# Motor_1.net
KiCad netlist of a schematic drawn in Altium Designer
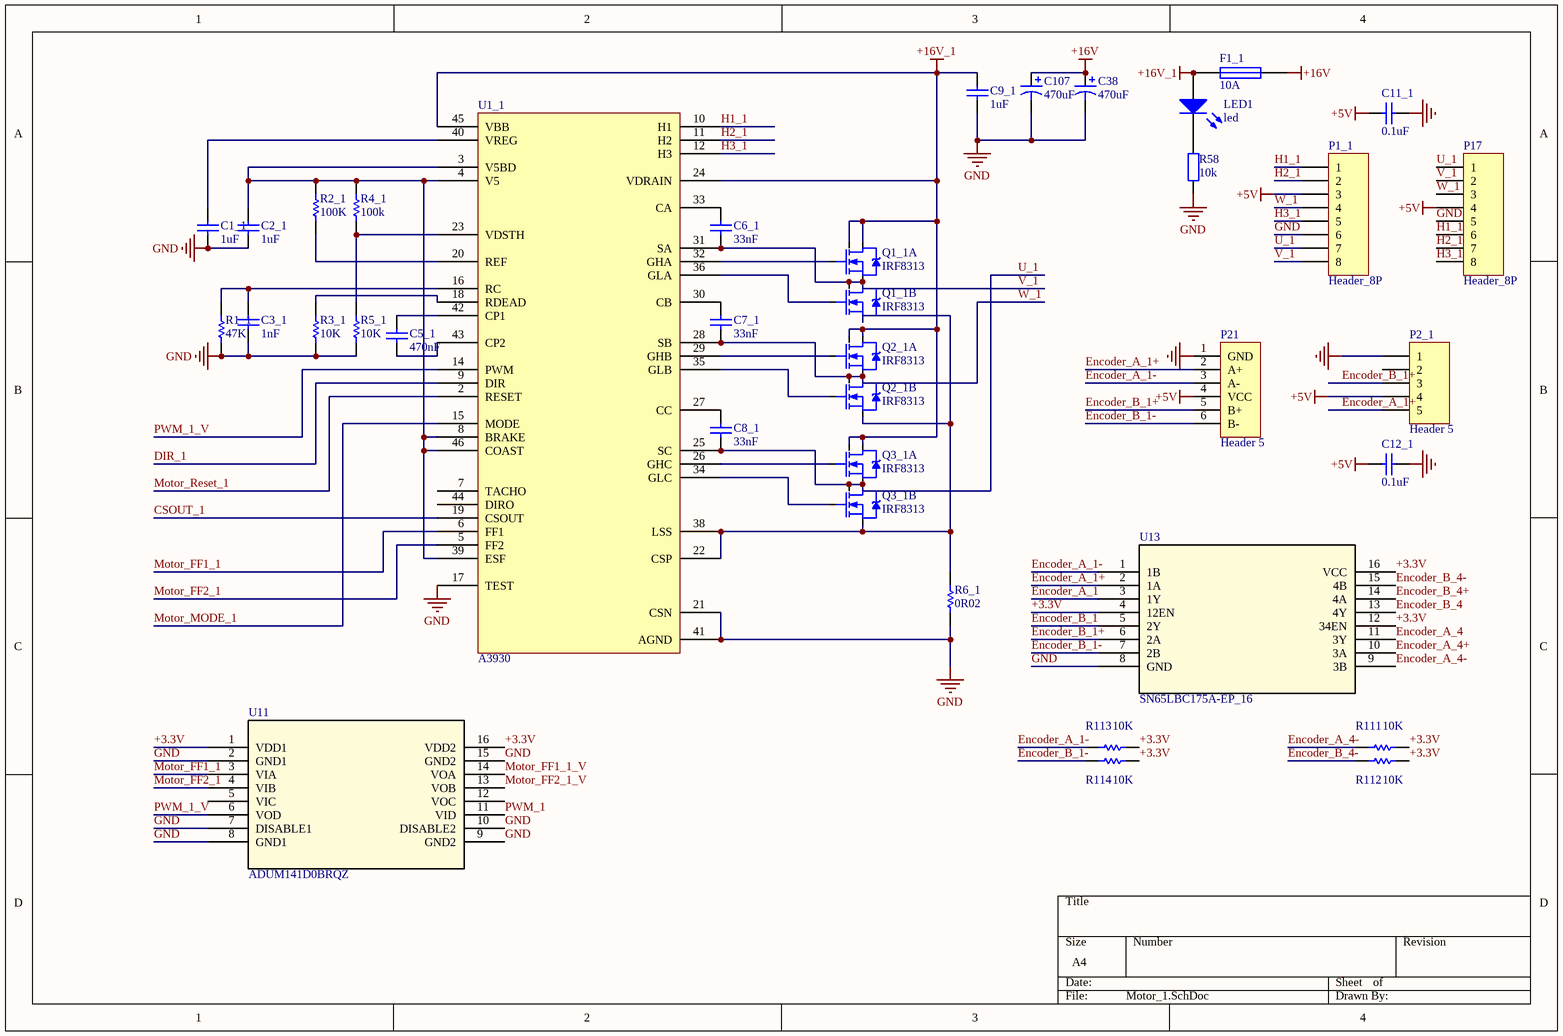
[diagram p0: Motor_1.SchDoc]

(export (version "E")
  (design (tool "Eeschema 10.0.6"))
  (components
    (comp (ref "C1_1")
      (value "1uF")
      (footprint "0603C")
      (description "Capacitor")
      (fields
        (field (name "MANUFACTURER") "Generic Components")
        (field (name "Comment") "1uf")
        (field (name "PUBLISHER") "Altium Hobart Technology Centre")
      )
      (libsource (lib "hp_2018_03") (part "Cap"))
    )
    (comp (ref "C2_1")
      (value "1uF")
      (footprint "0603C")
      (description "Capacitor")
      (fields
        (field (name "MANUFACTURER") "Generic Components")
        (field (name "Comment") "1uf")
        (field (name "PUBLISHER") "Altium Hobart Technology Centre")
      )
      (libsource (lib "hp_2018_03") (part "Cap"))
    )
    (comp (ref "C3_1")
      (value "1nF")
      (footprint "0603C")
      (description "Capacitor")
      (fields
        (field (name "MANUFACTURER") "Generic Components")
        (field (name "Comment") "1nf")
        (field (name "PUBLISHER") "Altium Hobart Technology Centre")
      )
      (libsource (lib "hp_2018_03") (part "Cap"))
    )
    (comp (ref "C5_1")
      (value "470nF")
      (footprint "0603C")
      (description "Capacitor")
      (fields
        (field (name "MANUFACTURER") "Generic Components")
        (field (name "Comment") "470nf")
        (field (name "PUBLISHER") "Altium Hobart Technology Centre")
      )
      (libsource (lib "hp_2018_03") (part "Cap"))
    )
    (comp (ref "C6_1")
      (value "33nF")
      (footprint "0603C")
      (description "Capacitor")
      (fields
        (field (name "MANUFACTURER") "Generic Components")
        (field (name "Comment") "33nf")
        (field (name "PUBLISHER") "Altium Hobart Technology Centre")
      )
      (libsource (lib "hp_2018_03") (part "Cap"))
    )
    (comp (ref "C7_1")
      (value "33nF")
      (footprint "0603C")
      (description "Capacitor")
      (fields
        (field (name "MANUFACTURER") "Generic Components")
        (field (name "Comment") "33nf")
        (field (name "PUBLISHER") "Altium Hobart Technology Centre")
      )
      (libsource (lib "hp_2018_03") (part "Cap"))
    )
    (comp (ref "C8_1")
      (value "33nF")
      (footprint "0603C")
      (description "Capacitor")
      (fields
        (field (name "MANUFACTURER") "Generic Components")
        (field (name "Comment") "33nf")
        (field (name "PUBLISHER") "Altium Hobart Technology Centre")
      )
      (libsource (lib "hp_2018_03") (part "Cap"))
    )
    (comp (ref "C9_1")
      (value "1uF")
      (footprint "0603C")
      (description "Capacitor")
      (fields
        (field (name "MANUFACTURER") "Generic Components")
        (field (name "Comment") "1uf")
        (field (name "PUBLISHER") "Altium Hobart Technology Centre")
      )
      (libsource (lib "hp_2018_03") (part "Cap"))
    )
    (comp (ref "C11_1")
      (value "0.1uF")
      (footprint "0603C")
      (description "Capacitor")
      (fields
        (field (name "MANUFACTURER") "Generic Components")
        (field (name "Comment") "0.1uf")
        (field (name "PUBLISHER") "Altium Hobart Technology Centre")
      )
      (libsource (lib "hp_2018_03") (part "Cap"))
    )
    (comp (ref "C12_1")
      (value "0.1uF")
      (footprint "0603C")
      (description "Capacitor")
      (fields
        (field (name "MANUFACTURER") "Generic Components")
        (field (name "Comment") "0.1uf")
        (field (name "PUBLISHER") "Altium Hobart Technology Centre")
      )
      (libsource (lib "hp_2018_03") (part "Cap"))
    )
    (comp (ref "C38")
      (value "470uF")
      (footprint "470uF")
      (description "Polarized Capacitor (Radial)")
      (fields (field (name "PUBLISHER") "Altium Limited"))
      (libsource (lib "Miscellaneous Devices") (part "Cap Pol1"))
    )
    (comp (ref "C107")
      (value "470uF")
      (footprint "470uF")
      (description "Polarized Capacitor (Radial)")
      (fields (field (name "PUBLISHER") "Altium Limited"))
      (libsource (lib "Miscellaneous Devices") (part "Cap Pol1"))
    )
    (comp (ref "F1_1")
      (value "10A")
      (footprint "Main_Board:FUSE_HEADER")
      (libsource (lib "Integrated_Library2") (part "FUSE"))
    )
    (comp (ref "LED1")
      (value "led")
      (footprint "0603_diode")
      (libsource (lib "Integrated_Library2") (part "led"))
    )
    (comp (ref "P1_1")
      (value "Header_8P")
      (footprint "8P - WF25122")
      (description "Used for Motor connection in ZJUNlict")
      (libsource (lib "Integrated_Library2") (part "Header_8P"))
    )
    (comp (ref "P2_1")
      (value "Header 5")
      (footprint "SHDR5")
      (description "Header, 5-Pin")
      (fields (field (name "PUBLISHER") "Altium Limited"))
      (libsource (lib "Miscellaneous Connectors") (part "Header 5"))
    )
    (comp (ref "P17")
      (value "Header_8P")
      (footprint "SHDR8")
      (description "Used for Motor connection in ZJUNlict")
      (libsource (lib "Integrated_Library2") (part "Header_8P"))
    )
    (comp (ref "P21")
      (value "Header 5")
      (footprint "SHDR6")
      (description "Header, 5-Pin")
      (fields (field (name "PUBLISHER") "Altium Limited"))
      (libsource (lib "Main_Board") (part "Header 6"))
    )
    (comp (ref "Q1_1") (value "IRF8313") (footprint "so-8 bg") (libsource (lib "BLDC") (part "SO-8 IRF8313")))
    (comp (ref "Q2_1") (value "IRF8313") (footprint "so-8 bg") (libsource (lib "BLDC") (part "SO-8 IRF8313")))
    (comp (ref "Q3_1") (value "IRF8313") (footprint "so-8 bg") (libsource (lib "BLDC") (part "SO-8 IRF8313")))
    (comp (ref "R1_1")
      (value "47K")
      (footprint "0603R")
      (description "Resistor")
      (fields
        (field (name "MANUFACTURER") "Generic Components")
        (field (name "Comment") "47k")
        (field (name "PUBLISHER") "Altium Hobart Technology Centre")
      )
      (libsource (lib "hp_2018_03") (part "Res1"))
    )
    (comp (ref "R2_1")
      (value "100K")
      (footprint "0603R")
      (description "Resistor")
      (fields
        (field (name "MANUFACTURER") "Generic Components")
        (field (name "Comment") "100k")
        (field (name "PUBLISHER") "Altium Hobart Technology Centre")
      )
      (libsource (lib "hp_2018_03") (part "Res1"))
    )
    (comp (ref "R3_1")
      (value "10K")
      (footprint "0603R")
      (description "Resistor")
      (fields
        (field (name "MANUFACTURER") "Generic Components")
        (field (name "Comment") "10k")
        (field (name "PUBLISHER") "Altium Hobart Technology Centre")
      )
      (libsource (lib "hp_2018_03") (part "Res1"))
    )
    (comp (ref "R4_1")
      (value "100k")
      (footprint "0603R")
      (description "Resistor")
      (fields
        (field (name "MANUFACTURER") "Generic Components")
        (field (name "PUBLISHER") "Altium Hobart Technology Centre")
      )
      (libsource (lib "hp_2018_03") (part "Res1"))
    )
    (comp (ref "R5_1")
      (value "10K")
      (footprint "0603R")
      (description "Resistor")
      (fields
        (field (name "MANUFACTURER") "Generic Components")
        (field (name "Comment") "10k")
        (field (name "PUBLISHER") "Altium Hobart Technology Centre")
      )
      (libsource (lib "hp_2018_03") (part "Res1"))
    )
    (comp (ref "R6_1")
      (value "0R02")
      (footprint "1206 10A")
      (description "Resistor")
      (fields
        (field (name "MANUFACTURER") "Generic Components")
        (field (name "Comment") "0.02")
        (field (name "PUBLISHER") "Altium Hobart Technology Centre")
      )
      (libsource (lib "hp_2018_03") (part "Res1"))
    )
    (comp (ref "R58") (value "10k") (footprint "0603") (libsource (lib "Integrated_Library2") (part "res")))
    (comp (ref "R111")
      (value "10K")
      (footprint "0603R")
      (description "Resistor")
      (fields
        (field (name "MANUFACTURER") "Generic Components")
        (field (name "Comment") "10k")
        (field (name "PUBLISHER") "Altium Hobart Technology Centre")
      )
      (libsource (lib "hp_2018_03") (part "Res1"))
    )
    (comp (ref "R112")
      (value "10K")
      (footprint "0603R")
      (description "Resistor")
      (fields
        (field (name "MANUFACTURER") "Generic Components")
        (field (name "Comment") "10k")
        (field (name "PUBLISHER") "Altium Hobart Technology Centre")
      )
      (libsource (lib "hp_2018_03") (part "Res1"))
    )
    (comp (ref "R113")
      (value "10K")
      (footprint "0603R")
      (description "Resistor")
      (fields
        (field (name "MANUFACTURER") "Generic Components")
        (field (name "Comment") "10k")
        (field (name "PUBLISHER") "Altium Hobart Technology Centre")
      )
      (libsource (lib "hp_2018_03") (part "Res1"))
    )
    (comp (ref "R114")
      (value "10K")
      (footprint "0603R")
      (description "Resistor")
      (fields
        (field (name "MANUFACTURER") "Generic Components")
        (field (name "Comment") "10k")
        (field (name "PUBLISHER") "Altium Hobart Technology Centre")
      )
      (libsource (lib "hp_2018_03") (part "Res1"))
    )
    (comp (ref "U1_1") (value "A3930") (footprint "LQFP-48") (libsource (lib "BLDC") (part "LQFP 48")))
    (comp (ref "U11")
      (value "ADUM141D0BRQZ")
      (footprint "Main_Board:RQ_16")
      (description "Imported")
      (libsource (lib "Main_Board") (part "ADUM141D0BRQZ"))
    )
    (comp (ref "U13")
      (value "SN65LBC175A-EP_16")
      (footprint "SOP16")
      (description "Quadruple 2-Input Positive-NAND Gates")
      (fields
        (field (name "MANUFACTURER") "Texas Instruments")
        (field (name "GENERIC_PART_NUMBER") "74AC11000")
      )
      (libsource (lib "Main_Board") (part "SN65LBC175A-EP_16"))
    )
  )
  (nets
    (net (code "1") (name "+5V") (class "Default")
      (node (ref "C11_1") (pin "2") (pinfunction "2_2") (pintype "passive"))
      (node (ref "C12_1") (pin "2") (pinfunction "2_2") (pintype "passive"))
      (node (ref "P17") (pin "4") (pinfunction "4_4") (pintype "passive"))
      (node (ref "P1_1") (pin "3") (pinfunction "3_3") (pintype "passive"))
      (node (ref "P21") (pin "4") (pinfunction "VCC_4") (pintype "passive"))
      (node (ref "P2_1") (pin "4") (pinfunction "4_4") (pintype "passive"))
    )
    (net (code "2") (name "+16V") (class "Default")
      (node (ref "C107") (pin "1") (pinfunction "1_1") (pintype "passive"))
      (node (ref "C38") (pin "1") (pinfunction "1_1") (pintype "passive"))
      (node (ref "F1_1") (pin "1") (pinfunction "1_1") (pintype "passive"))
    )
    (net (code "3") (name "+16V_1") (class "Default")
      (node (ref "C9_1") (pin "2") (pinfunction "2_2") (pintype "passive"))
      (node (ref "F1_1") (pin "2") (pinfunction "2_2") (pintype "passive"))
      (node (ref "LED1") (pin "1") (pinfunction "A_1") (pintype "passive"))
      (node (ref "Q1_1") (pin "7") (pinfunction "D2_7") (pintype "passive"))
      (node (ref "Q1_1") (pin "8") (pinfunction "D2_8") (pintype "passive"))
      (node (ref "Q2_1") (pin "7") (pinfunction "D2_7") (pintype "passive"))
      (node (ref "Q2_1") (pin "8") (pinfunction "D2_8") (pintype "passive"))
      (node (ref "Q3_1") (pin "7") (pinfunction "D2_7") (pintype "passive"))
      (node (ref "Q3_1") (pin "8") (pinfunction "D2_8") (pintype "passive"))
      (node (ref "U1_1") (pin "24") (pinfunction "VDRAIN_24") (pintype "passive"))
      (node (ref "U1_1") (pin "45") (pinfunction "VBB_45") (pintype "passive"))
    )
    (net (code "4") (name "/+3.3V") (class "Default")
      (node (ref "R111") (pin "1") (pinfunction "1_1") (pintype "passive"))
      (node (ref "R112") (pin "1") (pinfunction "1_1") (pintype "passive"))
      (node (ref "R113") (pin "1") (pinfunction "1_1") (pintype "passive"))
      (node (ref "R114") (pin "1") (pinfunction "1_1") (pintype "passive"))
      (node (ref "U11") (pin "1") (pinfunction "VDD1_1") (pintype "passive"))
      (node (ref "U11") (pin "16") (pinfunction "VDD2_16") (pintype "passive"))
      (node (ref "U13") (pin "12") (pinfunction "34EN_12") (pintype "passive"))
      (node (ref "U13") (pin "16") (pinfunction "VCC_16") (pintype "power_in"))
      (node (ref "U13") (pin "4") (pinfunction "12EN_4") (pintype "passive"))
    )
    (net (code "5") (name "/CSOUT_1") (class "Default")
      (node (ref "U1_1") (pin "19") (pinfunction "CSOUT_19") (pintype "passive"))
    )
    (net (code "6") (name "/DIR_1") (class "Default")
      (node (ref "U1_1") (pin "9") (pinfunction "DIR_9") (pintype "passive"))
    )
    (net (code "7") (name "/Encoder_A_1") (class "Default")
      (node (ref "U13") (pin "3") (pinfunction "1Y_3") (pintype "passive"))
    )
    (net (code "8") (name "/Encoder_A_1+") (class "Default")
      (node (ref "P21") (pin "2") (pinfunction "A+_2") (pintype "passive"))
      (node (ref "P2_1") (pin "5") (pinfunction "5_5") (pintype "passive"))
      (node (ref "U13") (pin "2") (pinfunction "1A_2") (pintype "passive"))
    )
    (net (code "9") (name "/Encoder_A_1-") (class "Default")
      (node (ref "P21") (pin "3") (pinfunction "A-_3") (pintype "passive"))
      (node (ref "R113") (pin "2") (pinfunction "2_2") (pintype "passive"))
      (node (ref "U13") (pin "1") (pinfunction "1B_1") (pintype "passive"))
    )
    (net (code "10") (name "/Encoder_A_4") (class "Default")
      (node (ref "U13") (pin "11") (pinfunction "3Y_11") (pintype "passive"))
    )
    (net (code "11") (name "/Encoder_A_4+") (class "Default")
      (node (ref "U13") (pin "10") (pinfunction "3A_10") (pintype "passive"))
    )
    (net (code "12") (name "/Encoder_A_4-") (class "Default")
      (node (ref "R111") (pin "2") (pinfunction "2_2") (pintype "passive"))
      (node (ref "U13") (pin "9") (pinfunction "3B_9") (pintype "passive"))
    )
    (net (code "13") (name "/Encoder_B_1") (class "Default")
      (node (ref "U13") (pin "5") (pinfunction "2Y_5") (pintype "passive"))
    )
    (net (code "14") (name "/Encoder_B_1+") (class "Default")
      (node (ref "P21") (pin "5") (pinfunction "B+_5") (pintype "passive"))
      (node (ref "P2_1") (pin "3") (pinfunction "3_3") (pintype "passive"))
      (node (ref "U13") (pin "6") (pinfunction "2A_6") (pintype "passive"))
    )
    (net (code "15") (name "/Encoder_B_1-") (class "Default")
      (node (ref "P21") (pin "6") (pinfunction "B-_6") (pintype "passive"))
      (node (ref "R114") (pin "2") (pinfunction "2_2") (pintype "passive"))
      (node (ref "U13") (pin "7") (pinfunction "2B_7") (pintype "passive"))
    )
    (net (code "16") (name "/Encoder_B_4") (class "Default")
      (node (ref "U13") (pin "13") (pinfunction "4Y_13") (pintype "passive"))
    )
    (net (code "17") (name "/Encoder_B_4+") (class "Default")
      (node (ref "U13") (pin "14") (pinfunction "4A_14") (pintype "passive"))
    )
    (net (code "18") (name "/Encoder_B_4-") (class "Default")
      (node (ref "R112") (pin "2") (pinfunction "2_2") (pintype "passive"))
      (node (ref "U13") (pin "15") (pinfunction "4B_15") (pintype "passive"))
    )
    (net (code "19") (name "/H1_1") (class "Default")
      (node (ref "P17") (pin "6") (pinfunction "6_6") (pintype "passive"))
      (node (ref "P1_1") (pin "1") (pinfunction "1_1") (pintype "passive"))
      (node (ref "U1_1") (pin "10") (pinfunction "H1_10") (pintype "passive"))
    )
    (net (code "20") (name "/H2_1") (class "Default")
      (node (ref "P17") (pin "7") (pinfunction "7_7") (pintype "passive"))
      (node (ref "P1_1") (pin "2") (pinfunction "2_2") (pintype "passive"))
      (node (ref "U1_1") (pin "11") (pinfunction "H2_11") (pintype "passive"))
    )
    (net (code "21") (name "/H3_1") (class "Default")
      (node (ref "P17") (pin "8") (pinfunction "8_8") (pintype "passive"))
      (node (ref "P1_1") (pin "5") (pinfunction "5_5") (pintype "passive"))
      (node (ref "U1_1") (pin "12") (pinfunction "H3_12") (pintype "passive"))
    )
    (net (code "22") (name "/Motor_FF1_1") (class "Default")
      (node (ref "U11") (pin "3") (pinfunction "VIA_3") (pintype "passive"))
      (node (ref "U1_1") (pin "6") (pinfunction "FF1_6") (pintype "passive"))
    )
    (net (code "23") (name "/Motor_FF1_1_V") (class "Default")
      (node (ref "U11") (pin "14") (pinfunction "VOA_14") (pintype "passive"))
    )
    (net (code "24") (name "/Motor_FF2_1") (class "Default")
      (node (ref "U11") (pin "4") (pinfunction "VIB_4") (pintype "passive"))
      (node (ref "U1_1") (pin "5") (pinfunction "FF2_5") (pintype "passive"))
    )
    (net (code "25") (name "/Motor_FF2_1_V") (class "Default")
      (node (ref "U11") (pin "13") (pinfunction "VOB_13") (pintype "passive"))
    )
    (net (code "26") (name "/Motor_MODE_1") (class "Default")
      (node (ref "U1_1") (pin "15") (pinfunction "MODE_15") (pintype "passive"))
    )
    (net (code "27") (name "/Motor_Reset_1") (class "Default")
      (node (ref "U1_1") (pin "2") (pinfunction "RESET_2") (pintype "passive"))
    )
    (net (code "28") (name "/PWM_1") (class "Default")
      (node (ref "U11") (pin "11") (pinfunction "VID_11") (pintype "passive"))
    )
    (net (code "29") (name "/PWM_1_V") (class "Default")
      (node (ref "U11") (pin "6") (pinfunction "VOD_6") (pintype "passive"))
      (node (ref "U1_1") (pin "14") (pinfunction "PWM_14") (pintype "passive"))
    )
    (net (code "30") (name "/U_1") (class "Default")
      (node (ref "C8_1") (pin "1") (pinfunction "1_1") (pintype "passive"))
      (node (ref "P17") (pin "1") (pinfunction "1_1") (pintype "passive"))
      (node (ref "P1_1") (pin "7") (pinfunction "7_7") (pintype "passive"))
      (node (ref "Q3_1") (pin "1") (pinfunction "S2_1") (pintype "passive"))
      (node (ref "Q3_1") (pin "5") (pinfunction "D1_5") (pintype "passive"))
      (node (ref "Q3_1") (pin "6") (pinfunction "D1_6") (pintype "passive"))
      (node (ref "U1_1") (pin "25") (pinfunction "SC_25") (pintype "passive"))
    )
    (net (code "31") (name "/V_1") (class "Default")
      (node (ref "C6_1") (pin "1") (pinfunction "1_1") (pintype "passive"))
      (node (ref "P17") (pin "2") (pinfunction "2_2") (pintype "passive"))
      (node (ref "P1_1") (pin "8") (pinfunction "8_8") (pintype "passive"))
      (node (ref "Q1_1") (pin "1") (pinfunction "S2_1") (pintype "passive"))
      (node (ref "Q1_1") (pin "5") (pinfunction "D1_5") (pintype "passive"))
      (node (ref "Q1_1") (pin "6") (pinfunction "D1_6") (pintype "passive"))
      (node (ref "U1_1") (pin "31") (pinfunction "SA_31") (pintype "passive"))
    )
    (net (code "32") (name "/W_1") (class "Default")
      (node (ref "C7_1") (pin "1") (pinfunction "1_1") (pintype "passive"))
      (node (ref "P17") (pin "3") (pinfunction "3_3") (pintype "passive"))
      (node (ref "P1_1") (pin "4") (pinfunction "4_4") (pintype "passive"))
      (node (ref "Q2_1") (pin "1") (pinfunction "S2_1") (pintype "passive"))
      (node (ref "Q2_1") (pin "5") (pinfunction "D1_5") (pintype "passive"))
      (node (ref "Q2_1") (pin "6") (pinfunction "D1_6") (pintype "passive"))
      (node (ref "U1_1") (pin "28") (pinfunction "SB_28") (pintype "passive"))
    )
    (net (code "33") (name "GND") (class "Default")
      (node (ref "C107") (pin "2") (pinfunction "2_2") (pintype "passive"))
      (node (ref "C11_1") (pin "1") (pinfunction "1_1") (pintype "passive"))
      (node (ref "C12_1") (pin "1") (pinfunction "1_1") (pintype "passive"))
      (node (ref "C1_1") (pin "1") (pinfunction "1_1") (pintype "passive"))
      (node (ref "C2_1") (pin "1") (pinfunction "1_1") (pintype "passive"))
      (node (ref "C38") (pin "2") (pinfunction "2_2") (pintype "passive"))
      (node (ref "C3_1") (pin "1") (pinfunction "1_1") (pintype "passive"))
      (node (ref "C9_1") (pin "1") (pinfunction "1_1") (pintype "passive"))
      (node (ref "P17") (pin "5") (pinfunction "5_5") (pintype "passive"))
      (node (ref "P1_1") (pin "6") (pinfunction "6_6") (pintype "passive"))
      (node (ref "P21") (pin "1") (pinfunction "GND_1") (pintype "passive"))
      (node (ref "P2_1") (pin "1") (pinfunction "1_1") (pintype "passive"))
      (node (ref "R1_1") (pin "1") (pinfunction "1_1") (pintype "passive"))
      (node (ref "R3_1") (pin "1") (pinfunction "1_1") (pintype "passive"))
      (node (ref "R58") (pin "1") (pinfunction "1_1") (pintype "passive"))
      (node (ref "R5_1") (pin "1") (pinfunction "1_1") (pintype "passive"))
      (node (ref "R6_1") (pin "1") (pinfunction "1_1") (pintype "passive"))
      (node (ref "U11") (pin "10") (pinfunction "DISABLE2_10") (pintype "passive"))
      (node (ref "U11") (pin "15") (pinfunction "GND2_15") (pintype "passive"))
      (node (ref "U11") (pin "2") (pinfunction "GND1_2") (pintype "passive"))
      (node (ref "U11") (pin "7") (pinfunction "DISABLE1_7") (pintype "passive"))
      (node (ref "U11") (pin "8") (pinfunction "GND1_8") (pintype "passive"))
      (node (ref "U11") (pin "9") (pinfunction "GND2_9") (pintype "passive"))
      (node (ref "U13") (pin "8") (pinfunction "GND_8") (pintype "passive"))
      (node (ref "U1_1") (pin "17") (pinfunction "TEST_17") (pintype "passive"))
      (node (ref "U1_1") (pin "21") (pinfunction "CSN_21") (pintype "passive"))
      (node (ref "U1_1") (pin "41") (pinfunction "AGND_41") (pintype "passive"))
    )
    (net (code "34") (name "Net-(LED1-K)") (class "Default")
      (node (ref "LED1") (pin "2") (pinfunction "K_2") (pintype "passive"))
      (node (ref "R58") (pin "2") (pinfunction "2_2") (pintype "passive"))
    )
    (net (code "35") (name "Net-(Q1_1A-G2)") (class "Default")
      (node (ref "Q1_1") (pin "2") (pinfunction "G2_2") (pintype "passive"))
      (node (ref "U1_1") (pin "32") (pinfunction "GHA_32") (pintype "passive"))
    )
    (net (code "36") (name "Net-(Q1_1B-G1)") (class "Default")
      (node (ref "Q1_1") (pin "4") (pinfunction "G1_4") (pintype "passive"))
      (node (ref "U1_1") (pin "36") (pinfunction "GLA_36") (pintype "passive"))
    )
    (net (code "37") (name "Net-(Q1_1B-S1)") (class "Default")
      (node (ref "Q1_1") (pin "3") (pinfunction "S1_3") (pintype "passive"))
      (node (ref "Q2_1") (pin "3") (pinfunction "S1_3") (pintype "passive"))
      (node (ref "Q3_1") (pin "3") (pinfunction "S1_3") (pintype "passive"))
      (node (ref "R6_1") (pin "2") (pinfunction "2_2") (pintype "passive"))
      (node (ref "U1_1") (pin "22") (pinfunction "CSP_22") (pintype "passive"))
      (node (ref "U1_1") (pin "38") (pinfunction "LSS_38") (pintype "passive"))
    )
    (net (code "38") (name "Net-(Q2_1A-G2)") (class "Default")
      (node (ref "Q2_1") (pin "2") (pinfunction "G2_2") (pintype "passive"))
      (node (ref "U1_1") (pin "29") (pinfunction "GHB_29") (pintype "passive"))
    )
    (net (code "39") (name "Net-(Q2_1B-G1)") (class "Default")
      (node (ref "Q2_1") (pin "4") (pinfunction "G1_4") (pintype "passive"))
      (node (ref "U1_1") (pin "35") (pinfunction "GLB_35") (pintype "passive"))
    )
    (net (code "40") (name "Net-(Q3_1A-G2)") (class "Default")
      (node (ref "Q3_1") (pin "2") (pinfunction "G2_2") (pintype "passive"))
      (node (ref "U1_1") (pin "26") (pinfunction "GHC_26") (pintype "passive"))
    )
    (net (code "41") (name "Net-(Q3_1B-G1)") (class "Default")
      (node (ref "Q3_1") (pin "4") (pinfunction "G1_4") (pintype "passive"))
      (node (ref "U1_1") (pin "34") (pinfunction "GLC_34") (pintype "passive"))
    )
    (net (code "42") (name "Net-(U1_1-BRAKE)") (class "Default")
      (node (ref "C2_1") (pin "2") (pinfunction "2_2") (pintype "passive"))
      (node (ref "R2_1") (pin "2") (pinfunction "2_2") (pintype "passive"))
      (node (ref "R4_1") (pin "2") (pinfunction "2_2") (pintype "passive"))
      (node (ref "U1_1") (pin "3") (pinfunction "V5BD_3") (pintype "passive"))
      (node (ref "U1_1") (pin "39") (pinfunction "ESF_39") (pintype "passive"))
      (node (ref "U1_1") (pin "4") (pinfunction "V5_4") (pintype "passive"))
      (node (ref "U1_1") (pin "46") (pinfunction "COAST_46") (pintype "passive"))
      (node (ref "U1_1") (pin "8") (pinfunction "BRAKE_8") (pintype "passive"))
    )
    (net (code "43") (name "Net-(U1_1-CA)") (class "Default")
      (node (ref "C6_1") (pin "2") (pinfunction "2_2") (pintype "passive"))
      (node (ref "U1_1") (pin "33") (pinfunction "CA_33") (pintype "passive"))
    )
    (net (code "44") (name "Net-(U1_1-CB)") (class "Default")
      (node (ref "C7_1") (pin "2") (pinfunction "2_2") (pintype "passive"))
      (node (ref "U1_1") (pin "30") (pinfunction "CB_30") (pintype "passive"))
    )
    (net (code "45") (name "Net-(U1_1-CC)") (class "Default")
      (node (ref "C8_1") (pin "2") (pinfunction "2_2") (pintype "passive"))
      (node (ref "U1_1") (pin "27") (pinfunction "CC_27") (pintype "passive"))
    )
    (net (code "46") (name "Net-(U1_1-CP1)") (class "Default")
      (node (ref "C5_1") (pin "2") (pinfunction "2_2") (pintype "passive"))
      (node (ref "U1_1") (pin "42") (pinfunction "CP1_42") (pintype "passive"))
    )
    (net (code "47") (name "Net-(U1_1-CP2)") (class "Default")
      (node (ref "C5_1") (pin "1") (pinfunction "1_1") (pintype "passive"))
      (node (ref "U1_1") (pin "43") (pinfunction "CP2_43") (pintype "passive"))
    )
    (net (code "48") (name "Net-(U1_1-RC)") (class "Default")
      (node (ref "C3_1") (pin "2") (pinfunction "2_2") (pintype "passive"))
      (node (ref "R1_1") (pin "2") (pinfunction "2_2") (pintype "passive"))
      (node (ref "U1_1") (pin "16") (pinfunction "RC_16") (pintype "passive"))
    )
    (net (code "49") (name "Net-(U1_1-RDEAD)") (class "Default")
      (node (ref "R3_1") (pin "2") (pinfunction "2_2") (pintype "passive"))
      (node (ref "U1_1") (pin "18") (pinfunction "RDEAD_18") (pintype "passive"))
    )
    (net (code "50") (name "Net-(U1_1-REF)") (class "Default")
      (node (ref "R2_1") (pin "1") (pinfunction "1_1") (pintype "passive"))
      (node (ref "U1_1") (pin "20") (pinfunction "REF_20") (pintype "passive"))
    )
    (net (code "51") (name "Net-(U1_1-VDSTH)") (class "Default")
      (node (ref "R4_1") (pin "1") (pinfunction "1_1") (pintype "passive"))
      (node (ref "R5_1") (pin "2") (pinfunction "2_2") (pintype "passive"))
      (node (ref "U1_1") (pin "23") (pinfunction "VDSTH_23") (pintype "passive"))
    )
    (net (code "52") (name "Net-(U1_1-VREG)") (class "Default")
      (node (ref "C1_1") (pin "2") (pinfunction "2_2") (pintype "passive"))
      (node (ref "U1_1") (pin "40") (pinfunction "VREG_40") (pintype "passive"))
    )
    (net (code "53") (name "unconnected-(P2_1-Pad2)") (class "Default")
      (node (ref "P2_1") (pin "2") (pinfunction "2_2") (pintype "passive"))
    )
    (net (code "54") (name "unconnected-(U1_1-DIRO-Pad44)") (class "Default")
      (node (ref "U1_1") (pin "44") (pinfunction "DIRO_44") (pintype "passive"))
    )
    (net (code "55") (name "unconnected-(U1_1-TACHO-Pad7)") (class "Default")
      (node (ref "U1_1") (pin "7") (pinfunction "TACHO_7") (pintype "passive"))
    )
    (net (code "56") (name "unconnected-(U11-VIC-Pad5)") (class "Default")
      (node (ref "U11") (pin "5") (pinfunction "VIC_5") (pintype "passive"))
    )
    (net (code "57") (name "unconnected-(U11-VOC-Pad12)") (class "Default")
      (node (ref "U11") (pin "12") (pinfunction "VOC_12") (pintype "passive"))
    )
  )
)
